# esp12.net
KiCad netlist of a schematic drawn in EAGLE
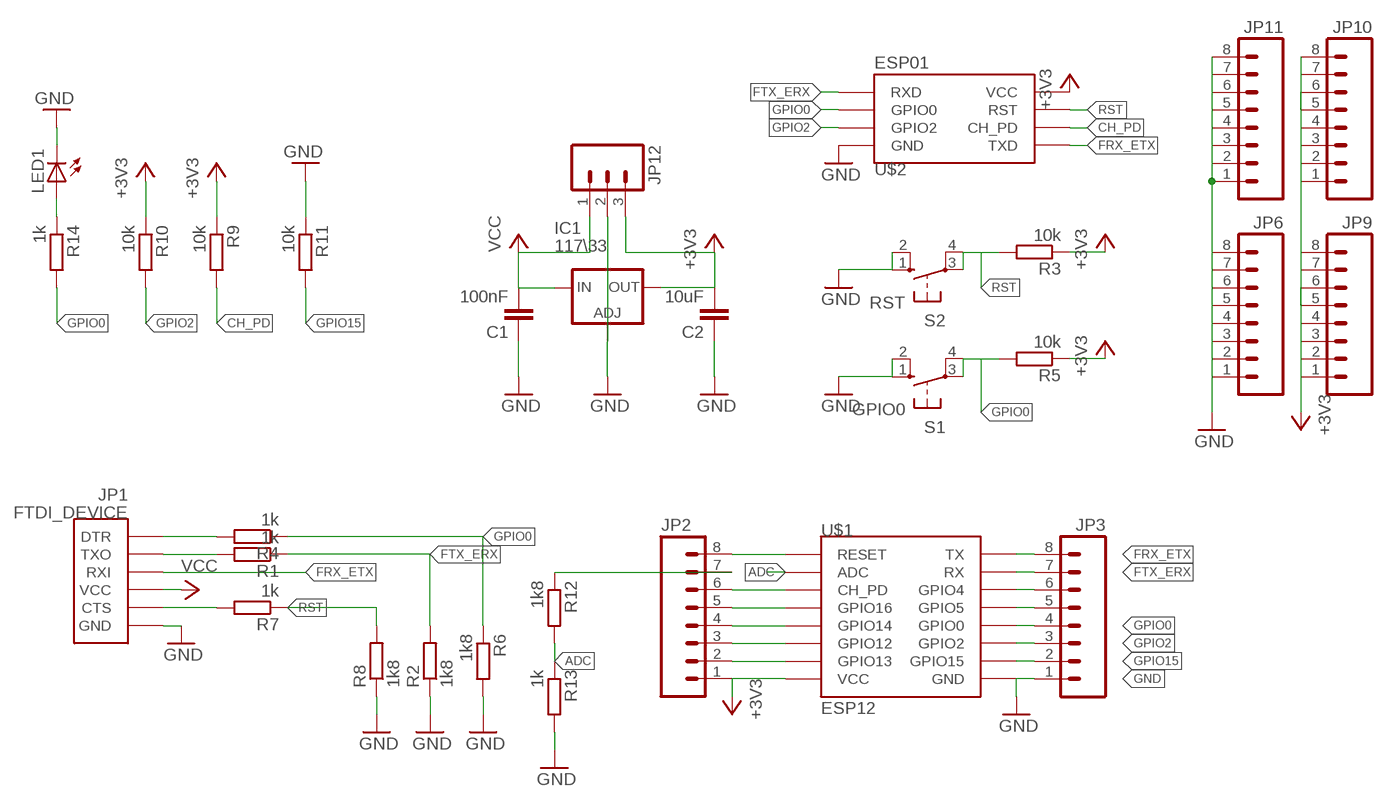
[diagram p0: schematic, sheet 1]

(export (version "E")
  (design (tool "Eeschema 10.0.6"))
  (components
    (comp (ref "C1")
      (value "100nF")
      (footprint "eagle-import:C1206")
      (libsource (lib "eagle-import") (part "C-EUC1206"))
    )
    (comp (ref "C2")
      (value "10uF")
      (footprint "eagle-import:C1206")
      (libsource (lib "eagle-import") (part "C-EUC1206"))
    )
    (comp (ref "IC1")
      (value "117\\33")
      (footprint "eagle-import:SOT223")
      (libsource (lib "eagle-import") (part "LD117A?S33TR"))
    )
    (comp (ref "JP1")
      (value "FTDI_DEVICE")
      (footprint "eagle-import:FTDI_DEVICE_SIDE")
      (libsource (lib "eagle-import") (part "FTDI_DEVICE"))
    )
    (comp (ref "JP2")
      (value "M08")
      (footprint "eagle-import:1X08_ROUND")
      (libsource (lib "eagle-import") (part "M08"))
    )
    (comp (ref "JP3")
      (value "M08")
      (footprint "eagle-import:1X08_ROUND")
      (libsource (lib "eagle-import") (part "M08"))
    )
    (comp (ref "JP6")
      (value "M08")
      (footprint "eagle-import:1X08_ROUND")
      (libsource (lib "eagle-import") (part "M08"))
    )
    (comp (ref "JP9")
      (value "M08")
      (footprint "eagle-import:1X08_ROUND")
      (libsource (lib "eagle-import") (part "M08"))
    )
    (comp (ref "JP10")
      (value "M08")
      (footprint "eagle-import:1X08_ROUND")
      (libsource (lib "eagle-import") (part "M08"))
    )
    (comp (ref "JP11")
      (value "M08")
      (footprint "eagle-import:1X08_ROUND")
      (libsource (lib "eagle-import") (part "M08"))
    )
    (comp (ref "JP12")
      (value "M03PTH")
      (footprint "eagle-import:1X03")
      (libsource (lib "eagle-import") (part "M03PTH"))
    )
    (comp (ref "LED1")
      (value "LEDSMT1206")
      (footprint "eagle-import:1206")
      (libsource (lib "eagle-import") (part "LEDSMT1206"))
    )
    (comp (ref "R1")
      (value "1k")
      (footprint "eagle-import:M1206")
      (libsource (lib "eagle-import") (part "R-EU_M1206"))
    )
    (comp (ref "R2")
      (value "1k8")
      (footprint "eagle-import:M1206")
      (libsource (lib "eagle-import") (part "R-EU_M1206"))
    )
    (comp (ref "R3")
      (value "10k")
      (footprint "eagle-import:M1206")
      (libsource (lib "eagle-import") (part "R-EU_M1206"))
    )
    (comp (ref "R4")
      (value "1k")
      (footprint "eagle-import:M1206")
      (libsource (lib "eagle-import") (part "R-EU_M1206"))
    )
    (comp (ref "R5")
      (value "10k")
      (footprint "eagle-import:M1206")
      (libsource (lib "eagle-import") (part "R-EU_M1206"))
    )
    (comp (ref "R6")
      (value "1k8")
      (footprint "eagle-import:M1206")
      (libsource (lib "eagle-import") (part "R-EU_M1206"))
    )
    (comp (ref "R7")
      (value "1k")
      (footprint "eagle-import:M1206")
      (libsource (lib "eagle-import") (part "R-EU_M1206"))
    )
    (comp (ref "R8")
      (value "1k8")
      (footprint "eagle-import:M1206")
      (libsource (lib "eagle-import") (part "R-EU_M1206"))
    )
    (comp (ref "R9")
      (value "10k")
      (footprint "eagle-import:M1206")
      (libsource (lib "eagle-import") (part "R-EU_M1206"))
    )
    (comp (ref "R10")
      (value "10k")
      (footprint "eagle-import:M1206")
      (libsource (lib "eagle-import") (part "R-EU_M1206"))
    )
    (comp (ref "R11")
      (value "10k")
      (footprint "eagle-import:M1206")
      (libsource (lib "eagle-import") (part "R-EU_M1206"))
    )
    (comp (ref "R12")
      (value "1k8")
      (footprint "eagle-import:M1206")
      (libsource (lib "eagle-import") (part "R-EU_M1206"))
    )
    (comp (ref "R13")
      (value "1k")
      (footprint "eagle-import:M1206")
      (libsource (lib "eagle-import") (part "R-EU_M1206"))
    )
    (comp (ref "R14")
      (value "1k")
      (footprint "eagle-import:M1206")
      (libsource (lib "eagle-import") (part "R-EU_M1206"))
    )
    (comp (ref "S1")
      (value "GPIO0")
      (footprint "eagle-import:B3F-10XX")
      (fields (field (name "MPN") "B3F-1000"))
      (libsource (lib "eagle-import") (part "10-XX"))
    )
    (comp (ref "S2")
      (value "RST")
      (footprint "eagle-import:B3F-10XX")
      (fields (field (name "MPN") "B3F-1000"))
      (libsource (lib "eagle-import") (part "10-XX"))
    )
    (comp (ref "U$1")
      (value "ESP12")
      (footprint "eagle-import:ESP12")
      (libsource (lib "eagle-import") (part "ESP12"))
    )
    (comp (ref "U$2")
      (value "ESP01")
      (footprint "eagle-import:ESP01")
      (libsource (lib "eagle-import") (part "ESP01"))
    )
  )
  (nets
    (net (code "1") (name "+3V3") (class "Default")
      (node (ref "C2") (pin "2") (pinfunction "2_2") (pintype "passive"))
      (node (ref "IC1") (pin "4") (pinfunction "OUT_4") (pintype "passive"))
      (node (ref "JP10") (pin "1") (pinfunction "1_1") (pintype "passive"))
      (node (ref "JP10") (pin "2") (pinfunction "2_2") (pintype "passive"))
      (node (ref "JP10") (pin "3") (pinfunction "3_3") (pintype "passive"))
      (node (ref "JP10") (pin "4") (pinfunction "4_4") (pintype "passive"))
      (node (ref "JP10") (pin "5") (pinfunction "5_5") (pintype "passive"))
      (node (ref "JP10") (pin "6") (pinfunction "6_6") (pintype "passive"))
      (node (ref "JP10") (pin "7") (pinfunction "7_7") (pintype "passive"))
      (node (ref "JP10") (pin "8") (pinfunction "8_8") (pintype "passive"))
      (node (ref "JP12") (pin "3") (pinfunction "3_3") (pintype "passive"))
      (node (ref "JP2") (pin "1") (pinfunction "1_1") (pintype "passive"))
      (node (ref "JP9") (pin "1") (pinfunction "1_1") (pintype "passive"))
      (node (ref "JP9") (pin "2") (pinfunction "2_2") (pintype "passive"))
      (node (ref "JP9") (pin "3") (pinfunction "3_3") (pintype "passive"))
      (node (ref "JP9") (pin "4") (pinfunction "4_4") (pintype "passive"))
      (node (ref "JP9") (pin "5") (pinfunction "5_5") (pintype "passive"))
      (node (ref "JP9") (pin "6") (pinfunction "6_6") (pintype "passive"))
      (node (ref "JP9") (pin "7") (pinfunction "7_7") (pintype "passive"))
      (node (ref "JP9") (pin "8") (pinfunction "8_8") (pintype "passive"))
      (node (ref "R10") (pin "1") (pinfunction "1_1") (pintype "passive"))
      (node (ref "R3") (pin "1") (pinfunction "1_1") (pintype "passive"))
      (node (ref "R5") (pin "1") (pinfunction "1_1") (pintype "passive"))
      (node (ref "R9") (pin "1") (pinfunction "1_1") (pintype "passive"))
      (node (ref "U$1") (pin "VCC") (pinfunction "VCC_VCC") (pintype "bidirectional"))
      (node (ref "U$2") (pin "VCC") (pinfunction "VCC_VCC") (pintype "bidirectional"))
    )
    (net (code "2") (name "ADC") (class "Default")
      (node (ref "R12") (pin "2") (pinfunction "2_2") (pintype "passive"))
      (node (ref "R13") (pin "1") (pinfunction "1_1") (pintype "passive"))
      (node (ref "U$1") (pin "ADC") (pinfunction "ADC_ADC") (pintype "bidirectional"))
    )
    (net (code "3") (name "CH_PD") (class "Default")
      (node (ref "JP2") (pin "6") (pinfunction "6_6") (pintype "passive"))
      (node (ref "R9") (pin "2") (pinfunction "2_2") (pintype "passive"))
      (node (ref "U$1") (pin "CH_PD") (pinfunction "CH_PD_CH_PD") (pintype "bidirectional"))
      (node (ref "U$2") (pin "CH_PD") (pinfunction "CH_PD_CH_PD") (pintype "bidirectional"))
    )
    (net (code "4") (name "FRX_ETX") (class "Default")
      (node (ref "JP1") (pin "P$3") (pinfunction "RXI_P$3") (pintype "bidirectional"))
      (node (ref "JP3") (pin "8") (pinfunction "8_8") (pintype "passive"))
      (node (ref "U$1") (pin "TX") (pinfunction "TX_TX") (pintype "bidirectional"))
      (node (ref "U$2") (pin "TX") (pinfunction "TXD_TX") (pintype "bidirectional"))
    )
    (net (code "5") (name "FTX_ERX") (class "Default")
      (node (ref "JP3") (pin "7") (pinfunction "7_7") (pintype "passive"))
      (node (ref "R1") (pin "1") (pinfunction "1_1") (pintype "passive"))
      (node (ref "R2") (pin "2") (pinfunction "2_2") (pintype "passive"))
      (node (ref "U$1") (pin "RX") (pinfunction "RX_RX") (pintype "bidirectional"))
      (node (ref "U$2") (pin "RX") (pinfunction "RXD_RX") (pintype "bidirectional"))
    )
    (net (code "6") (name "GND") (class "Default")
      (node (ref "C1") (pin "1") (pinfunction "1_1") (pintype "passive"))
      (node (ref "C2") (pin "1") (pinfunction "1_1") (pintype "passive"))
      (node (ref "IC1") (pin "1") (pinfunction "ADJ_1") (pintype "input"))
      (node (ref "JP1") (pin "P$6") (pinfunction "GND_P$6") (pintype "bidirectional"))
      (node (ref "JP11") (pin "1") (pinfunction "1_1") (pintype "passive"))
      (node (ref "JP11") (pin "2") (pinfunction "2_2") (pintype "passive"))
      (node (ref "JP11") (pin "3") (pinfunction "3_3") (pintype "passive"))
      (node (ref "JP11") (pin "4") (pinfunction "4_4") (pintype "passive"))
      (node (ref "JP11") (pin "5") (pinfunction "5_5") (pintype "passive"))
      (node (ref "JP11") (pin "6") (pinfunction "6_6") (pintype "passive"))
      (node (ref "JP11") (pin "7") (pinfunction "7_7") (pintype "passive"))
      (node (ref "JP11") (pin "8") (pinfunction "8_8") (pintype "passive"))
      (node (ref "JP12") (pin "2") (pinfunction "2_2") (pintype "passive"))
      (node (ref "JP3") (pin "1") (pinfunction "1_1") (pintype "passive"))
      (node (ref "JP6") (pin "1") (pinfunction "1_1") (pintype "passive"))
      (node (ref "JP6") (pin "2") (pinfunction "2_2") (pintype "passive"))
      (node (ref "JP6") (pin "3") (pinfunction "3_3") (pintype "passive"))
      (node (ref "JP6") (pin "4") (pinfunction "4_4") (pintype "passive"))
      (node (ref "JP6") (pin "5") (pinfunction "5_5") (pintype "passive"))
      (node (ref "JP6") (pin "6") (pinfunction "6_6") (pintype "passive"))
      (node (ref "JP6") (pin "7") (pinfunction "7_7") (pintype "passive"))
      (node (ref "JP6") (pin "8") (pinfunction "8_8") (pintype "passive"))
      (node (ref "LED1") (pin "C") (pinfunction "C_C") (pintype "passive"))
      (node (ref "R11") (pin "1") (pinfunction "1_1") (pintype "passive"))
      (node (ref "R13") (pin "2") (pinfunction "2_2") (pintype "passive"))
      (node (ref "R2") (pin "1") (pinfunction "1_1") (pintype "passive"))
      (node (ref "R6") (pin "2") (pinfunction "2_2") (pintype "passive"))
      (node (ref "R8") (pin "1") (pinfunction "1_1") (pintype "passive"))
      (node (ref "S1") (pin "1") (pinfunction "S_1") (pintype "passive"))
      (node (ref "S1") (pin "2") (pinfunction "S1_2") (pintype "passive"))
      (node (ref "S2") (pin "1") (pinfunction "S_1") (pintype "passive"))
      (node (ref "S2") (pin "2") (pinfunction "S1_2") (pintype "passive"))
      (node (ref "U$1") (pin "GND") (pinfunction "GND_GND") (pintype "bidirectional"))
      (node (ref "U$2") (pin "GND") (pinfunction "GND_GND") (pintype "bidirectional"))
    )
    (net (code "7") (name "GPIO0") (class "Default")
      (node (ref "JP3") (pin "4") (pinfunction "4_4") (pintype "passive"))
      (node (ref "R14") (pin "2") (pinfunction "2_2") (pintype "passive"))
      (node (ref "R4") (pin "1") (pinfunction "1_1") (pintype "passive"))
      (node (ref "R5") (pin "2") (pinfunction "2_2") (pintype "passive"))
      (node (ref "R6") (pin "1") (pinfunction "1_1") (pintype "passive"))
      (node (ref "S1") (pin "3") (pinfunction "P_3") (pintype "passive"))
      (node (ref "S1") (pin "4") (pinfunction "P1_4") (pintype "passive"))
      (node (ref "U$1") (pin "GPIO0") (pinfunction "GPIO0_GPIO0") (pintype "bidirectional"))
      (node (ref "U$2") (pin "GPIO0") (pinfunction "GPIO0_GPIO0") (pintype "bidirectional"))
    )
    (net (code "8") (name "GPIO2") (class "Default")
      (node (ref "JP3") (pin "3") (pinfunction "3_3") (pintype "passive"))
      (node (ref "R10") (pin "2") (pinfunction "2_2") (pintype "passive"))
      (node (ref "U$1") (pin "GPIO2") (pinfunction "GPIO2_GPIO2") (pintype "bidirectional"))
      (node (ref "U$2") (pin "GPIO2") (pinfunction "GPIO2_GPIO2") (pintype "bidirectional"))
    )
    (net (code "9") (name "GPIO15") (class "Default")
      (node (ref "JP3") (pin "2") (pinfunction "2_2") (pintype "passive"))
      (node (ref "R11") (pin "2") (pinfunction "2_2") (pintype "passive"))
      (node (ref "U$1") (pin "GPIO15") (pinfunction "GPIO15_GPIO15") (pintype "bidirectional"))
    )
    (net (code "10") (name "Net-(JP1-CTS)") (class "Default")
      (node (ref "JP1") (pin "P$5") (pinfunction "CTS_P$5") (pintype "bidirectional"))
      (node (ref "R7") (pin "2") (pinfunction "2_2") (pintype "passive"))
    )
    (net (code "11") (name "Net-(JP1-DTR)") (class "Default")
      (node (ref "JP1") (pin "P$1") (pinfunction "DTR_P$1") (pintype "bidirectional"))
      (node (ref "R4") (pin "2") (pinfunction "2_2") (pintype "passive"))
    )
    (net (code "12") (name "Net-(JP1-TXO)") (class "Default")
      (node (ref "JP1") (pin "P$2") (pinfunction "TXO_P$2") (pintype "bidirectional"))
      (node (ref "R1") (pin "2") (pinfunction "2_2") (pintype "passive"))
    )
    (net (code "13") (name "Net-(JP2-Pad2)") (class "Default")
      (node (ref "JP2") (pin "2") (pinfunction "2_2") (pintype "passive"))
      (node (ref "U$1") (pin "GPIO13") (pinfunction "GPIO13_GPIO13") (pintype "bidirectional"))
    )
    (net (code "14") (name "Net-(JP2-Pad3)") (class "Default")
      (node (ref "JP2") (pin "3") (pinfunction "3_3") (pintype "passive"))
      (node (ref "U$1") (pin "GPIO12") (pinfunction "GPIO12_GPIO12") (pintype "bidirectional"))
    )
    (net (code "15") (name "Net-(JP2-Pad4)") (class "Default")
      (node (ref "JP2") (pin "4") (pinfunction "4_4") (pintype "passive"))
      (node (ref "U$1") (pin "GPIO14") (pinfunction "GPIO14_GPIO14") (pintype "bidirectional"))
    )
    (net (code "16") (name "Net-(JP2-Pad5)") (class "Default")
      (node (ref "JP2") (pin "5") (pinfunction "5_5") (pintype "passive"))
      (node (ref "U$1") (pin "GPIO16") (pinfunction "GPIO16_GPIO16") (pintype "bidirectional"))
    )
    (net (code "17") (name "Net-(JP2-Pad7)") (class "Default")
      (node (ref "JP2") (pin "7") (pinfunction "7_7") (pintype "passive"))
      (node (ref "R12") (pin "1") (pinfunction "1_1") (pintype "passive"))
    )
    (net (code "18") (name "Net-(JP3-Pad5)") (class "Default")
      (node (ref "JP3") (pin "5") (pinfunction "5_5") (pintype "passive"))
      (node (ref "U$1") (pin "GPIO5") (pinfunction "GPIO5_GPIO5") (pintype "bidirectional"))
    )
    (net (code "19") (name "Net-(JP3-Pad6)") (class "Default")
      (node (ref "JP3") (pin "6") (pinfunction "6_6") (pintype "passive"))
      (node (ref "U$1") (pin "GPIO4") (pinfunction "GPIO4_GPIO4") (pintype "bidirectional"))
    )
    (net (code "20") (name "Net-(LED1-PadA)") (class "Default")
      (node (ref "LED1") (pin "A") (pinfunction "A_A") (pintype "passive"))
      (node (ref "R14") (pin "1") (pinfunction "1_1") (pintype "passive"))
    )
    (net (code "21") (name "RST") (class "Default")
      (node (ref "JP2") (pin "8") (pinfunction "8_8") (pintype "passive"))
      (node (ref "R3") (pin "2") (pinfunction "2_2") (pintype "passive"))
      (node (ref "R7") (pin "1") (pinfunction "1_1") (pintype "passive"))
      (node (ref "R8") (pin "2") (pinfunction "2_2") (pintype "passive"))
      (node (ref "S2") (pin "3") (pinfunction "P_3") (pintype "passive"))
      (node (ref "S2") (pin "4") (pinfunction "P1_4") (pintype "passive"))
      (node (ref "U$1") (pin "RESET") (pinfunction "RESET_RESET") (pintype "bidirectional"))
      (node (ref "U$2") (pin "RST") (pinfunction "RST_RST") (pintype "bidirectional"))
    )
    (net (code "22") (name "VCC") (class "Default")
      (node (ref "C1") (pin "2") (pinfunction "2_2") (pintype "passive"))
      (node (ref "IC1") (pin "3") (pinfunction "IN_3") (pintype "input"))
      (node (ref "JP1") (pin "P$4") (pinfunction "VCC_P$4") (pintype "bidirectional"))
      (node (ref "JP12") (pin "1") (pinfunction "1_1") (pintype "passive"))
    )
  )
)
